# main_1_0.net
KiCad netlist of a schematic drawn in EAGLE
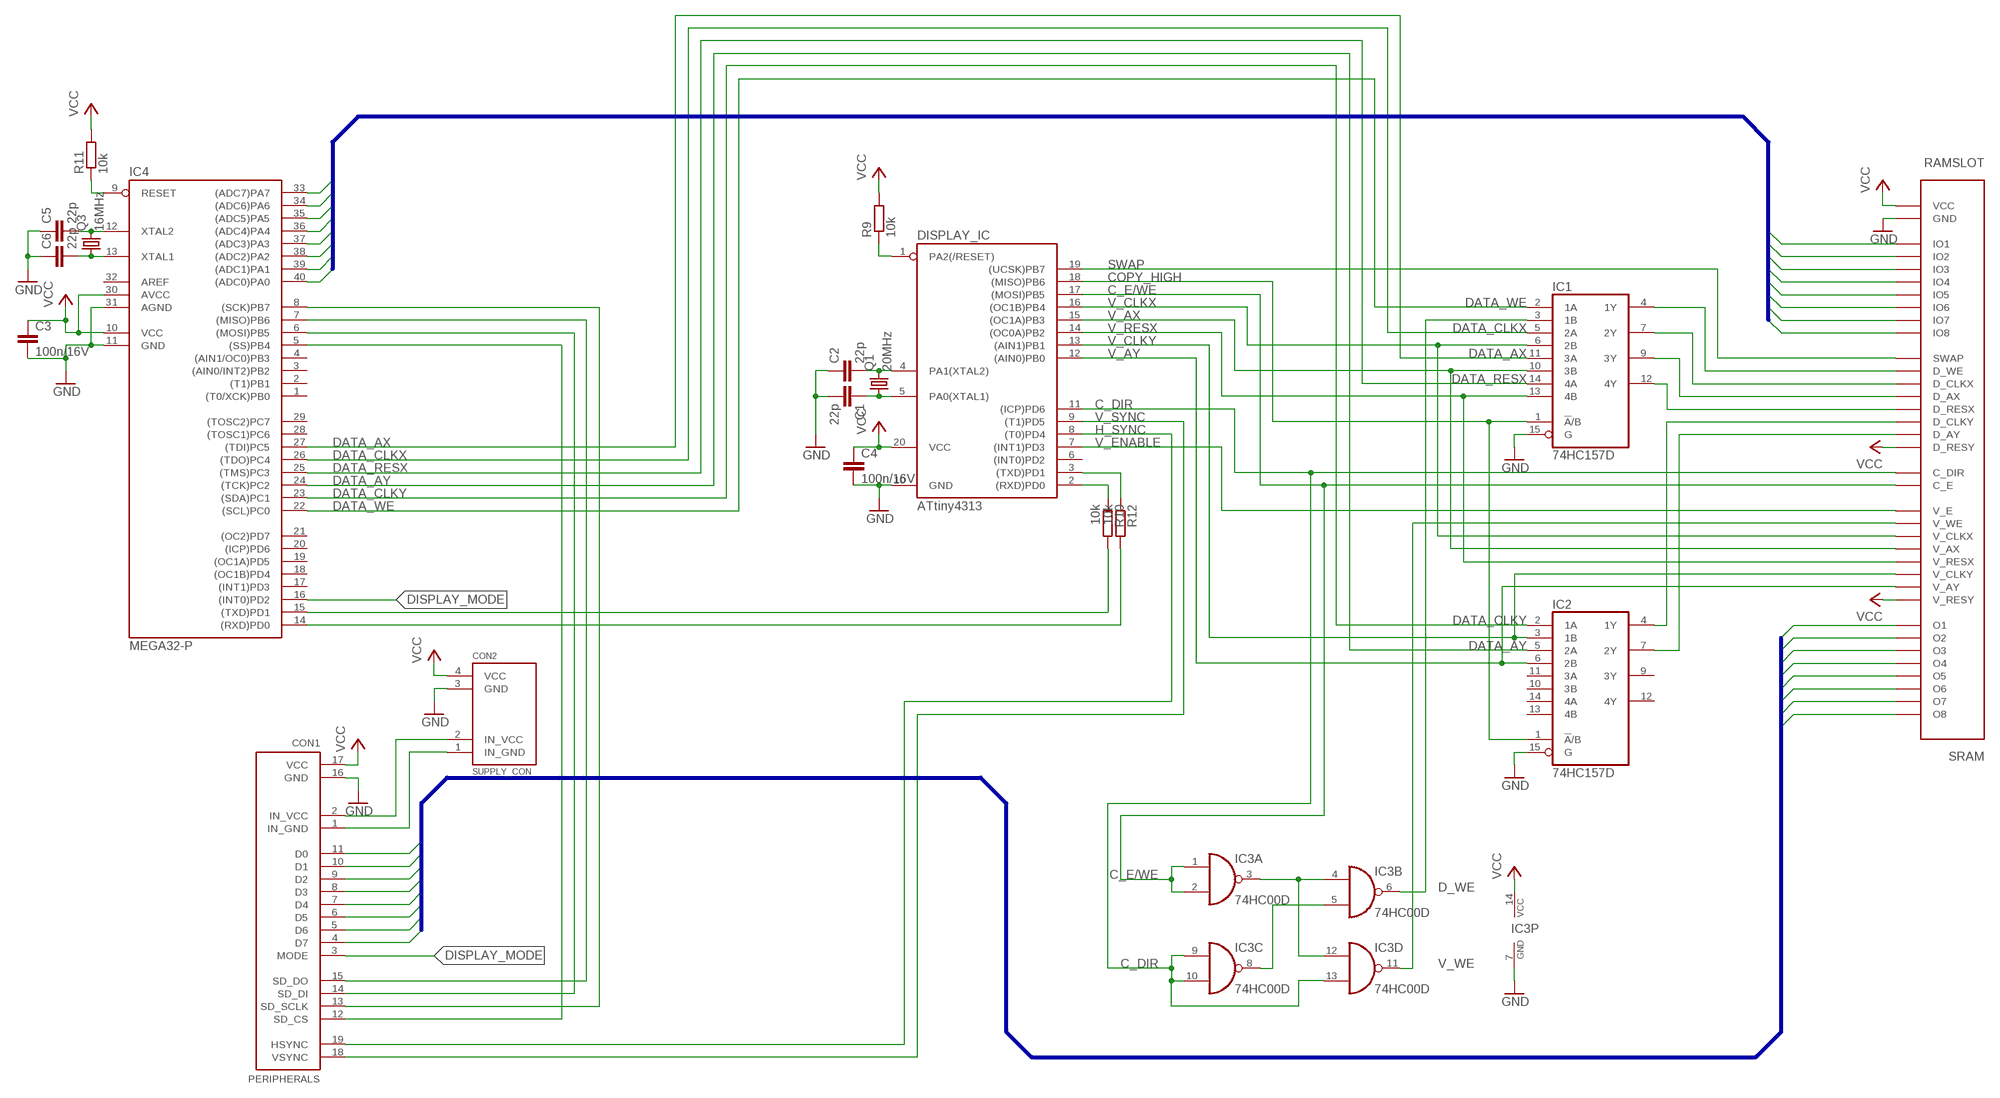
[diagram p0: schematic, sheet 1]

(export (version "E")
  (design (tool "Eeschema 10.0.6"))
  (components
    (comp (ref "C1")
      (value "22p")
      (footprint "eagle-import:C0603")
      (libsource (lib "eagle-import") (part "C-EUC0603"))
    )
    (comp (ref "C2")
      (value "22p")
      (footprint "eagle-import:C0603")
      (libsource (lib "eagle-import") (part "C-EUC0603"))
    )
    (comp (ref "C3")
      (value "100n/16V")
      (footprint "eagle-import:C0603")
      (libsource (lib "eagle-import") (part "C-EUC0603"))
    )
    (comp (ref "C4")
      (value "100n/16V")
      (footprint "eagle-import:C0603")
      (libsource (lib "eagle-import") (part "C-EUC0603"))
    )
    (comp (ref "C5")
      (value "22p")
      (footprint "eagle-import:C0603")
      (libsource (lib "eagle-import") (part "C-EUC0603"))
    )
    (comp (ref "C6")
      (value "22p")
      (footprint "eagle-import:C0603")
      (libsource (lib "eagle-import") (part "C-EUC0603"))
    )
    (comp (ref "CON1")
      (value "PERIPHERALS")
      (footprint "eagle-import:PERIPHERALS_CON")
      (libsource (lib "eagle-import") (part "PERIPHERALS"))
    )
    (comp (ref "CON2")
      (value "SUPPLY_CON")
      (footprint "eagle-import:SUPPLY_CON")
      (libsource (lib "eagle-import") (part "SUPPLY_CON"))
    )
    (comp (ref "DISPLAY_IC")
      (value "ATtiny4313")
      (footprint "eagle-import:DIL20")
      (libsource (lib "eagle-import") (part "TINY2313-P"))
    )
    (comp (ref "IC1")
      (value "74HC157D")
      (footprint "eagle-import:SO16")
      (libsource (lib "eagle-import") (part "74157DHC"))
    )
    (comp (ref "IC2")
      (value "74HC157D")
      (footprint "eagle-import:SO16")
      (libsource (lib "eagle-import") (part "74157DHC"))
    )
    (comp (ref "IC3")
      (value "74HC00D")
      (footprint "eagle-import:SO14")
      (libsource (lib "eagle-import") (part "7400DHC"))
    )
    (comp (ref "IC4")
      (value "MEGA32-P")
      (footprint "eagle-import:DIL40")
      (libsource (lib "eagle-import") (part "MEGA32-P"))
    )
    (comp (ref "Q1")
      (value "20MHz")
      (footprint "eagle-import:HC49")
      (libsource (lib "eagle-import") (part "CRYSTALS-NOGND-HC49"))
    )
    (comp (ref "Q3")
      (value "16MHz")
      (footprint "eagle-import:HC49")
      (libsource (lib "eagle-import") (part "CRYSTALS-NOGND-HC49"))
    )
    (comp (ref "R9")
      (value "10k")
      (footprint "eagle-import:R0603")
      (libsource (lib "eagle-import") (part "R-EU_R0603"))
    )
    (comp (ref "R10")
      (value "10k")
      (footprint "eagle-import:R0603")
      (libsource (lib "eagle-import") (part "R-EU_R0603"))
    )
    (comp (ref "R11")
      (value "10k")
      (footprint "eagle-import:R0603")
      (libsource (lib "eagle-import") (part "R-EU_R0603"))
    )
    (comp (ref "R12")
      (value "10k")
      (footprint "eagle-import:R0603")
      (libsource (lib "eagle-import") (part "R-EU_R0603"))
    )
    (comp (ref "RAMSLOT")
      (value "SRAM")
      (footprint "eagle-import:SLOT")
      (libsource (lib "eagle-import") (part "SLOT"))
    )
  )
  (nets
    (net (code "1") (name "/AREF") (class "Default")
      (node (ref "IC4") (pin "32") (pinfunction "AREF_32") (pintype "power_in"))
    )
    (net (code "2") (name "/COPY_HIGH") (class "Default")
      (node (ref "DISPLAY_IC") (pin "18") (pinfunction "(MISO)PB6_18") (pintype "bidirectional"))
      (node (ref "IC1") (pin "1") (pinfunction "~{A}/B_1") (pintype "input"))
      (node (ref "IC2") (pin "1") (pinfunction "~{A}/B_1") (pintype "input"))
    )
    (net (code "3") (name "/C_DIR") (class "Default")
      (node (ref "DISPLAY_IC") (pin "11") (pinfunction "(ICP)PD6_11") (pintype "bidirectional"))
      (node (ref "IC3") (pin "10") (pinfunction "I1_10") (pintype "input"))
      (node (ref "IC3") (pin "13") (pinfunction "I1_13") (pintype "input"))
      (node (ref "IC3") (pin "9") (pinfunction "I0_9") (pintype "input"))
      (node (ref "RAMSLOT") (pin "C_DIR") (pinfunction "C_DIR_C_DIR") (pintype "bidirectional"))
      (node (ref "RAMSLOT") (pin "C_DIRB") (pinfunction "C_DIR_C_DIRB") (pintype "bidirectional"))
    )
    (net (code "4") (name "/C_E{slash}WE") (class "Default")
      (node (ref "DISPLAY_IC") (pin "17") (pinfunction "(MOSI)PB5_17") (pintype "bidirectional"))
      (node (ref "IC3") (pin "1") (pinfunction "I0_1") (pintype "input"))
      (node (ref "IC3") (pin "2") (pinfunction "I1_2") (pintype "input"))
      (node (ref "RAMSLOT") (pin "C_E") (pinfunction "C_E_C_E") (pintype "bidirectional"))
      (node (ref "RAMSLOT") (pin "C_EB") (pinfunction "C_E_C_EB") (pintype "bidirectional"))
    )
    (net (code "5") (name "/DATA0") (class "Default")
      (node (ref "IC4") (pin "40") (pinfunction "(ADC0)PA0_40") (pintype "bidirectional"))
      (node (ref "RAMSLOT") (pin "IO1") (pinfunction "IO1_IO1") (pintype "bidirectional"))
      (node (ref "RAMSLOT") (pin "IO1B") (pinfunction "IO1_IO1B") (pintype "bidirectional"))
    )
    (net (code "6") (name "/DATA1") (class "Default")
      (node (ref "IC4") (pin "39") (pinfunction "(ADC1)PA1_39") (pintype "bidirectional"))
      (node (ref "RAMSLOT") (pin "IO2") (pinfunction "IO2_IO2") (pintype "bidirectional"))
      (node (ref "RAMSLOT") (pin "IO2B") (pinfunction "IO2_IO2B") (pintype "bidirectional"))
    )
    (net (code "7") (name "/DATA2") (class "Default")
      (node (ref "IC4") (pin "38") (pinfunction "(ADC2)PA2_38") (pintype "bidirectional"))
      (node (ref "RAMSLOT") (pin "IO3") (pinfunction "IO3_IO3") (pintype "bidirectional"))
      (node (ref "RAMSLOT") (pin "IO3B") (pinfunction "IO3_IO3B") (pintype "bidirectional"))
    )
    (net (code "8") (name "/DATA3") (class "Default")
      (node (ref "IC4") (pin "37") (pinfunction "(ADC3)PA3_37") (pintype "bidirectional"))
      (node (ref "RAMSLOT") (pin "IO4") (pinfunction "IO4_IO4") (pintype "bidirectional"))
      (node (ref "RAMSLOT") (pin "IO4B") (pinfunction "IO4_IO4B") (pintype "bidirectional"))
    )
    (net (code "9") (name "/DATA4") (class "Default")
      (node (ref "IC4") (pin "36") (pinfunction "(ADC4)PA4_36") (pintype "bidirectional"))
      (node (ref "RAMSLOT") (pin "IO5") (pinfunction "IO5_IO5") (pintype "bidirectional"))
      (node (ref "RAMSLOT") (pin "IO5B") (pinfunction "IO5_IO5B") (pintype "bidirectional"))
    )
    (net (code "10") (name "/DATA5") (class "Default")
      (node (ref "IC4") (pin "35") (pinfunction "(ADC5)PA5_35") (pintype "bidirectional"))
      (node (ref "RAMSLOT") (pin "IO6") (pinfunction "IO6_IO6") (pintype "bidirectional"))
      (node (ref "RAMSLOT") (pin "IO6B") (pinfunction "IO6_IO6B") (pintype "bidirectional"))
    )
    (net (code "11") (name "/DATA6") (class "Default")
      (node (ref "IC4") (pin "34") (pinfunction "(ADC6)PA6_34") (pintype "bidirectional"))
      (node (ref "RAMSLOT") (pin "IO7") (pinfunction "IO7_IO7") (pintype "bidirectional"))
      (node (ref "RAMSLOT") (pin "IO7B") (pinfunction "IO7_IO7B") (pintype "bidirectional"))
    )
    (net (code "12") (name "/DATA7") (class "Default")
      (node (ref "IC4") (pin "33") (pinfunction "(ADC7)PA7_33") (pintype "bidirectional"))
      (node (ref "RAMSLOT") (pin "IO8") (pinfunction "IO8_IO8") (pintype "bidirectional"))
      (node (ref "RAMSLOT") (pin "IO8B") (pinfunction "IO8_IO8B") (pintype "bidirectional"))
    )
    (net (code "13") (name "/DATA_AX") (class "Default")
      (node (ref "IC1") (pin "11") (pinfunction "3A_11") (pintype "input"))
      (node (ref "IC4") (pin "27") (pinfunction "(TDI)PC5_27") (pintype "bidirectional"))
    )
    (net (code "14") (name "/DATA_AY") (class "Default")
      (node (ref "IC2") (pin "5") (pinfunction "2A_5") (pintype "input"))
      (node (ref "IC4") (pin "24") (pinfunction "(TCK)PC2_24") (pintype "bidirectional"))
    )
    (net (code "15") (name "/DATA_CLKX") (class "Default")
      (node (ref "IC1") (pin "5") (pinfunction "2A_5") (pintype "input"))
      (node (ref "IC4") (pin "26") (pinfunction "(TDO)PC4_26") (pintype "bidirectional"))
    )
    (net (code "16") (name "/DATA_CLKY") (class "Default")
      (node (ref "IC2") (pin "2") (pinfunction "1A_2") (pintype "input"))
      (node (ref "IC4") (pin "23") (pinfunction "(SDA)PC1_23") (pintype "bidirectional"))
    )
    (net (code "17") (name "/DATA_RESX") (class "Default")
      (node (ref "IC1") (pin "14") (pinfunction "4A_14") (pintype "input"))
      (node (ref "IC4") (pin "25") (pinfunction "(TMS)PC3_25") (pintype "bidirectional"))
    )
    (net (code "18") (name "/DATA_WE") (class "Default")
      (node (ref "IC1") (pin "2") (pinfunction "1A_2") (pintype "input"))
      (node (ref "IC4") (pin "22") (pinfunction "(SCL)PC0_22") (pintype "bidirectional"))
    )
    (net (code "19") (name "/D_WE") (class "Default")
      (node (ref "IC1") (pin "3") (pinfunction "1B_3") (pintype "input"))
      (node (ref "IC3") (pin "6") (pinfunction "O_6") (pintype "output"))
    )
    (net (code "20") (name "/H_SYNC") (class "Default")
      (node (ref "CON1") (pin "19") (pinfunction "HSYNC_19") (pintype "bidirectional"))
      (node (ref "DISPLAY_IC") (pin "8") (pinfunction "(T0)PD4_8") (pintype "bidirectional"))
    )
    (net (code "21") (name "/O0") (class "Default")
      (node (ref "CON1") (pin "11") (pinfunction "D0_11") (pintype "bidirectional"))
      (node (ref "RAMSLOT") (pin "O1") (pinfunction "O1_O1") (pintype "bidirectional"))
      (node (ref "RAMSLOT") (pin "O1B") (pinfunction "O1_O1B") (pintype "bidirectional"))
    )
    (net (code "22") (name "/O1") (class "Default")
      (node (ref "CON1") (pin "10") (pinfunction "D1_10") (pintype "bidirectional"))
      (node (ref "RAMSLOT") (pin "O2") (pinfunction "O2_O2") (pintype "bidirectional"))
      (node (ref "RAMSLOT") (pin "O2B") (pinfunction "O2_O2B") (pintype "bidirectional"))
    )
    (net (code "23") (name "/O2") (class "Default")
      (node (ref "CON1") (pin "9") (pinfunction "D2_9") (pintype "bidirectional"))
      (node (ref "RAMSLOT") (pin "O3") (pinfunction "O3_O3") (pintype "bidirectional"))
      (node (ref "RAMSLOT") (pin "O3B") (pinfunction "O3_O3B") (pintype "bidirectional"))
    )
    (net (code "24") (name "/O3") (class "Default")
      (node (ref "CON1") (pin "8") (pinfunction "D3_8") (pintype "bidirectional"))
      (node (ref "RAMSLOT") (pin "O4") (pinfunction "O4_O4") (pintype "bidirectional"))
      (node (ref "RAMSLOT") (pin "O4B") (pinfunction "O4_O4B") (pintype "bidirectional"))
    )
    (net (code "25") (name "/O4") (class "Default")
      (node (ref "CON1") (pin "7") (pinfunction "D4_7") (pintype "bidirectional"))
      (node (ref "RAMSLOT") (pin "O5") (pinfunction "O5_O5") (pintype "bidirectional"))
      (node (ref "RAMSLOT") (pin "O5B") (pinfunction "O5_O5B") (pintype "bidirectional"))
    )
    (net (code "26") (name "/O5") (class "Default")
      (node (ref "CON1") (pin "6") (pinfunction "D5_6") (pintype "bidirectional"))
      (node (ref "RAMSLOT") (pin "O6") (pinfunction "O6_O6") (pintype "bidirectional"))
      (node (ref "RAMSLOT") (pin "O6B") (pinfunction "O6_O6B") (pintype "bidirectional"))
    )
    (net (code "27") (name "/O6") (class "Default")
      (node (ref "CON1") (pin "5") (pinfunction "D6_5") (pintype "bidirectional"))
      (node (ref "RAMSLOT") (pin "O7") (pinfunction "O7_O7") (pintype "bidirectional"))
      (node (ref "RAMSLOT") (pin "O7B") (pinfunction "O7_O7B") (pintype "bidirectional"))
    )
    (net (code "28") (name "/O7") (class "Default")
      (node (ref "CON1") (pin "4") (pinfunction "D7_4") (pintype "bidirectional"))
      (node (ref "RAMSLOT") (pin "O8") (pinfunction "O8_O8") (pintype "bidirectional"))
      (node (ref "RAMSLOT") (pin "O8B") (pinfunction "O8_O8B") (pintype "bidirectional"))
    )
    (net (code "29") (name "/SWAP") (class "Default")
      (node (ref "DISPLAY_IC") (pin "19") (pinfunction "(UCSK)PB7_19") (pintype "bidirectional"))
      (node (ref "RAMSLOT") (pin "SWAP") (pinfunction "SWAP_SWAP") (pintype "bidirectional"))
      (node (ref "RAMSLOT") (pin "SWAPB") (pinfunction "SWAP_SWAPB") (pintype "bidirectional"))
    )
    (net (code "30") (name "/V_AX") (class "Default")
      (node (ref "DISPLAY_IC") (pin "15") (pinfunction "(OC1A)PB3_15") (pintype "bidirectional"))
      (node (ref "IC1") (pin "10") (pinfunction "3B_10") (pintype "input"))
      (node (ref "RAMSLOT") (pin "V_AX") (pinfunction "V_AX_V_AX") (pintype "bidirectional"))
      (node (ref "RAMSLOT") (pin "V_AXB") (pinfunction "V_AX_V_AXB") (pintype "bidirectional"))
    )
    (net (code "31") (name "/V_AY") (class "Default")
      (node (ref "DISPLAY_IC") (pin "12") (pinfunction "(AIN0)PB0_12") (pintype "bidirectional"))
      (node (ref "IC2") (pin "6") (pinfunction "2B_6") (pintype "input"))
      (node (ref "RAMSLOT") (pin "V_AY") (pinfunction "V_AY_V_AY") (pintype "bidirectional"))
      (node (ref "RAMSLOT") (pin "V_AYB") (pinfunction "V_AY_V_AYB") (pintype "bidirectional"))
    )
    (net (code "32") (name "/V_CLKX") (class "Default")
      (node (ref "DISPLAY_IC") (pin "16") (pinfunction "(OC1B)PB4_16") (pintype "bidirectional"))
      (node (ref "IC1") (pin "6") (pinfunction "2B_6") (pintype "input"))
      (node (ref "RAMSLOT") (pin "V_CLKX") (pinfunction "V_CLKX_V_CLKX") (pintype "bidirectional"))
      (node (ref "RAMSLOT") (pin "V_CLKXB") (pinfunction "V_CLKX_V_CLKXB") (pintype "bidirectional"))
    )
    (net (code "33") (name "/V_CLKY") (class "Default")
      (node (ref "DISPLAY_IC") (pin "13") (pinfunction "(AIN1)PB1_13") (pintype "bidirectional"))
      (node (ref "IC2") (pin "3") (pinfunction "1B_3") (pintype "input"))
      (node (ref "RAMSLOT") (pin "V_CLKY") (pinfunction "V_CLKY_V_CLKY") (pintype "bidirectional"))
      (node (ref "RAMSLOT") (pin "V_CLKYB") (pinfunction "V_CLKY_V_CLKYB") (pintype "bidirectional"))
    )
    (net (code "34") (name "/V_ENABLE") (class "Default")
      (node (ref "DISPLAY_IC") (pin "7") (pinfunction "(INT1)PD3_7") (pintype "bidirectional"))
      (node (ref "RAMSLOT") (pin "V_E") (pinfunction "V_E_V_E") (pintype "bidirectional"))
      (node (ref "RAMSLOT") (pin "V_EB") (pinfunction "V_E_V_EB") (pintype "bidirectional"))
    )
    (net (code "35") (name "/V_RESX") (class "Default")
      (node (ref "DISPLAY_IC") (pin "14") (pinfunction "(OC0A)PB2_14") (pintype "bidirectional"))
      (node (ref "IC1") (pin "13") (pinfunction "4B_13") (pintype "input"))
      (node (ref "RAMSLOT") (pin "V_RESX") (pinfunction "V_RESX_V_RESX") (pintype "bidirectional"))
      (node (ref "RAMSLOT") (pin "V_RESXB") (pinfunction "V_RESX_V_RESXB") (pintype "bidirectional"))
    )
    (net (code "36") (name "/V_SYNC") (class "Default")
      (node (ref "CON1") (pin "18") (pinfunction "VSYNC_18") (pintype "bidirectional"))
      (node (ref "DISPLAY_IC") (pin "9") (pinfunction "(T1)PD5_9") (pintype "bidirectional"))
    )
    (net (code "37") (name "/V_WE") (class "Default")
      (node (ref "IC3") (pin "11") (pinfunction "O_11") (pintype "output"))
      (node (ref "RAMSLOT") (pin "V_WE") (pinfunction "V_WE_V_WE") (pintype "bidirectional"))
      (node (ref "RAMSLOT") (pin "V_WEB") (pinfunction "V_WE_V_WEB") (pintype "bidirectional"))
    )
    (net (code "38") (name "DISPLAY_MODE") (class "Default")
      (node (ref "CON1") (pin "3") (pinfunction "MODE_3") (pintype "bidirectional"))
      (node (ref "IC4") (pin "16") (pinfunction "(INT0)PD2_16") (pintype "bidirectional"))
    )
    (net (code "39") (name "GND") (class "Default")
      (node (ref "C1") (pin "2") (pinfunction "2_2") (pintype "passive"))
      (node (ref "C2") (pin "1") (pinfunction "1_1") (pintype "passive"))
      (node (ref "C3") (pin "2") (pinfunction "2_2") (pintype "passive"))
      (node (ref "C4") (pin "2") (pinfunction "2_2") (pintype "passive"))
      (node (ref "C5") (pin "1") (pinfunction "1_1") (pintype "passive"))
      (node (ref "C6") (pin "1") (pinfunction "1_1") (pintype "passive"))
      (node (ref "CON1") (pin "16") (pinfunction "GND_16") (pintype "power_in"))
      (node (ref "CON2") (pin "3") (pinfunction "GND_3") (pintype "bidirectional"))
      (node (ref "DISPLAY_IC") (pin "10") (pinfunction "GND_10") (pintype "power_in"))
      (node (ref "IC1") (pin "15") (pinfunction "G_15") (pintype "input"))
      (node (ref "IC2") (pin "15") (pinfunction "G_15") (pintype "input"))
      (node (ref "IC3") (pin "7") (pinfunction "GND_7") (pintype "power_in"))
      (node (ref "IC4") (pin "11") (pinfunction "GND_11") (pintype "power_in"))
      (node (ref "IC4") (pin "31") (pinfunction "AGND_31") (pintype "power_in"))
      (node (ref "RAMSLOT") (pin "GND") (pinfunction "GND_GND") (pintype "bidirectional"))
      (node (ref "RAMSLOT") (pin "GNDB") (pinfunction "GND_GNDB") (pintype "bidirectional"))
    )
    (net (code "40") (name "Net-(CON1-IN_GND)") (class "Default")
      (node (ref "CON1") (pin "1") (pinfunction "IN_GND_1") (pintype "power_in"))
      (node (ref "CON2") (pin "1") (pinfunction "IN_GND_1") (pintype "bidirectional"))
    )
    (net (code "41") (name "Net-(CON1-IN_VCC)") (class "Default")
      (node (ref "CON1") (pin "2") (pinfunction "IN_VCC_2") (pintype "power_in"))
      (node (ref "CON2") (pin "2") (pinfunction "IN_VCC_2") (pintype "bidirectional"))
    )
    (net (code "42") (name "Net-(CON1-SD_CS)") (class "Default")
      (node (ref "CON1") (pin "12") (pinfunction "SD_CS_12") (pintype "bidirectional"))
      (node (ref "IC4") (pin "5") (pinfunction "(SS)PB4_5") (pintype "bidirectional"))
    )
    (net (code "43") (name "Net-(CON1-SD_DI)") (class "Default")
      (node (ref "CON1") (pin "14") (pinfunction "SD_DI_14") (pintype "bidirectional"))
      (node (ref "IC4") (pin "6") (pinfunction "(MOSI)PB5_6") (pintype "bidirectional"))
    )
    (net (code "44") (name "Net-(CON1-SD_DO)") (class "Default")
      (node (ref "CON1") (pin "15") (pinfunction "SD_DO_15") (pintype "bidirectional"))
      (node (ref "IC4") (pin "7") (pinfunction "(MISO)PB6_7") (pintype "bidirectional"))
    )
    (net (code "45") (name "Net-(CON1-SD_SCLK)") (class "Default")
      (node (ref "CON1") (pin "13") (pinfunction "SD_SCLK_13") (pintype "bidirectional"))
      (node (ref "IC4") (pin "8") (pinfunction "(SCK)PB7_8") (pintype "bidirectional"))
    )
    (net (code "46") (name "Net-(DISPLAY_IC-(RXD)PD0)") (class "Default")
      (node (ref "DISPLAY_IC") (pin "2") (pinfunction "(RXD)PD0_2") (pintype "bidirectional"))
      (node (ref "R10") (pin "1") (pinfunction "1_1") (pintype "passive"))
    )
    (net (code "47") (name "Net-(DISPLAY_IC-(TXD)PD1)") (class "Default")
      (node (ref "DISPLAY_IC") (pin "3") (pinfunction "(TXD)PD1_3") (pintype "bidirectional"))
      (node (ref "R12") (pin "1") (pinfunction "1_1") (pintype "passive"))
    )
    (net (code "48") (name "Net-(DISPLAY_IC-PA0(XTAL1))") (class "Default")
      (node (ref "C1") (pin "1") (pinfunction "1_1") (pintype "passive"))
      (node (ref "DISPLAY_IC") (pin "5") (pinfunction "PA0(XTAL1)_5") (pintype "bidirectional"))
      (node (ref "Q1") (pin "1") (pinfunction "1_1") (pintype "passive"))
    )
    (net (code "49") (name "Net-(DISPLAY_IC-PA1(XTAL2))") (class "Default")
      (node (ref "C2") (pin "2") (pinfunction "2_2") (pintype "passive"))
      (node (ref "DISPLAY_IC") (pin "4") (pinfunction "PA1(XTAL2)_4") (pintype "bidirectional"))
      (node (ref "Q1") (pin "2") (pinfunction "2_2") (pintype "passive"))
    )
    (net (code "50") (name "Net-(DISPLAY_IC-PA2({slash}RESET))") (class "Default")
      (node (ref "DISPLAY_IC") (pin "1") (pinfunction "PA2(/RESET)_1") (pintype "input"))
      (node (ref "R9") (pin "1") (pinfunction "1_1") (pintype "passive"))
    )
    (net (code "51") (name "Net-(IC1A-1Y)") (class "Default")
      (node (ref "IC1") (pin "4") (pinfunction "1Y_4") (pintype "output"))
      (node (ref "RAMSLOT") (pin "D_WE") (pinfunction "D_WE_D_WE") (pintype "bidirectional"))
      (node (ref "RAMSLOT") (pin "D_WEB") (pinfunction "D_WE_D_WEB") (pintype "bidirectional"))
    )
    (net (code "52") (name "Net-(IC1A-2Y)") (class "Default")
      (node (ref "IC1") (pin "7") (pinfunction "2Y_7") (pintype "output"))
      (node (ref "RAMSLOT") (pin "D_CLKX") (pinfunction "D_CLKX_D_CLKX") (pintype "bidirectional"))
      (node (ref "RAMSLOT") (pin "D_CLKXB") (pinfunction "D_CLKX_D_CLKXB") (pintype "bidirectional"))
    )
    (net (code "53") (name "Net-(IC1A-3Y)") (class "Default")
      (node (ref "IC1") (pin "9") (pinfunction "3Y_9") (pintype "output"))
      (node (ref "RAMSLOT") (pin "D_AX") (pinfunction "D_AX_D_AX") (pintype "bidirectional"))
      (node (ref "RAMSLOT") (pin "D_AXB") (pinfunction "D_AX_D_AXB") (pintype "bidirectional"))
    )
    (net (code "54") (name "Net-(IC1A-4Y)") (class "Default")
      (node (ref "IC1") (pin "12") (pinfunction "4Y_12") (pintype "output"))
      (node (ref "RAMSLOT") (pin "D_RESX") (pinfunction "D_RESX_D_RESX") (pintype "bidirectional"))
      (node (ref "RAMSLOT") (pin "D_RESXB") (pinfunction "D_RESX_D_RESXB") (pintype "bidirectional"))
    )
    (net (code "55") (name "Net-(IC2A-1Y)") (class "Default")
      (node (ref "IC2") (pin "4") (pinfunction "1Y_4") (pintype "output"))
      (node (ref "RAMSLOT") (pin "D_CLKY") (pinfunction "D_CLKY_D_CLKY") (pintype "bidirectional"))
      (node (ref "RAMSLOT") (pin "D_CLKYB") (pinfunction "D_CLKY_D_CLKYB") (pintype "bidirectional"))
    )
    (net (code "56") (name "Net-(IC2A-2Y)") (class "Default")
      (node (ref "IC2") (pin "7") (pinfunction "2Y_7") (pintype "output"))
      (node (ref "RAMSLOT") (pin "D_AY") (pinfunction "D_AY_D_AY") (pintype "bidirectional"))
      (node (ref "RAMSLOT") (pin "D_AYB") (pinfunction "D_AY_D_AYB") (pintype "bidirectional"))
    )
    (net (code "57") (name "Net-(IC3A-O)") (class "Default")
      (node (ref "IC3") (pin "12") (pinfunction "I0_12") (pintype "input"))
      (node (ref "IC3") (pin "3") (pinfunction "O_3") (pintype "output"))
      (node (ref "IC3") (pin "4") (pinfunction "I0_4") (pintype "input"))
    )
    (net (code "58") (name "Net-(IC3B-I1)") (class "Default")
      (node (ref "IC3") (pin "5") (pinfunction "I1_5") (pintype "input"))
      (node (ref "IC3") (pin "8") (pinfunction "O_8") (pintype "output"))
    )
    (net (code "59") (name "Net-(IC4-(RXD)PD0)") (class "Default")
      (node (ref "IC4") (pin "14") (pinfunction "(RXD)PD0_14") (pintype "bidirectional"))
      (node (ref "R12") (pin "2") (pinfunction "2_2") (pintype "passive"))
    )
    (net (code "60") (name "Net-(IC4-(TXD)PD1)") (class "Default")
      (node (ref "IC4") (pin "15") (pinfunction "(TXD)PD1_15") (pintype "bidirectional"))
      (node (ref "R10") (pin "2") (pinfunction "2_2") (pintype "passive"))
    )
    (net (code "61") (name "Net-(IC4-RESET)") (class "Default")
      (node (ref "IC4") (pin "9") (pinfunction "RESET_9") (pintype "input"))
      (node (ref "R11") (pin "1") (pinfunction "1_1") (pintype "passive"))
    )
    (net (code "62") (name "Net-(IC4-XTAL1)") (class "Default")
      (node (ref "C6") (pin "2") (pinfunction "2_2") (pintype "passive"))
      (node (ref "IC4") (pin "13") (pinfunction "XTAL1_13") (pintype "bidirectional"))
      (node (ref "Q3") (pin "1") (pinfunction "1_1") (pintype "passive"))
    )
    (net (code "63") (name "Net-(IC4-XTAL2)") (class "Default")
      (node (ref "C5") (pin "2") (pinfunction "2_2") (pintype "passive"))
      (node (ref "IC4") (pin "12") (pinfunction "XTAL2_12") (pintype "bidirectional"))
      (node (ref "Q3") (pin "2") (pinfunction "2_2") (pintype "passive"))
    )
    (net (code "64") (name "VCC") (class "Default")
      (node (ref "C3") (pin "1") (pinfunction "1_1") (pintype "passive"))
      (node (ref "C4") (pin "1") (pinfunction "1_1") (pintype "passive"))
      (node (ref "CON1") (pin "17") (pinfunction "VCC_17") (pintype "power_in"))
      (node (ref "CON2") (pin "4") (pinfunction "VCC_4") (pintype "bidirectional"))
      (node (ref "DISPLAY_IC") (pin "20") (pinfunction "VCC_20") (pintype "power_in"))
      (node (ref "IC3") (pin "14") (pinfunction "VCC_14") (pintype "power_in"))
      (node (ref "IC4") (pin "10") (pinfunction "VCC_10") (pintype "power_in"))
      (node (ref "IC4") (pin "30") (pinfunction "AVCC_30") (pintype "power_in"))
      (node (ref "R11") (pin "2") (pinfunction "2_2") (pintype "passive"))
      (node (ref "R9") (pin "2") (pinfunction "2_2") (pintype "passive"))
      (node (ref "RAMSLOT") (pin "D_RESY") (pinfunction "D_RESY_D_RESY") (pintype "bidirectional"))
      (node (ref "RAMSLOT") (pin "D_RESYB") (pinfunction "D_RESY_D_RESYB") (pintype "bidirectional"))
      (node (ref "RAMSLOT") (pin "VCC") (pinfunction "VCC_VCC") (pintype "bidirectional"))
      (node (ref "RAMSLOT") (pin "VCCB") (pinfunction "VCC_VCCB") (pintype "bidirectional"))
      (node (ref "RAMSLOT") (pin "V_RESY") (pinfunction "V_RESY_V_RESY") (pintype "bidirectional"))
      (node (ref "RAMSLOT") (pin "V_RESYB") (pinfunction "V_RESY_V_RESYB") (pintype "bidirectional"))
    )
    (net (code "65") (name "unconnected-(DISPLAY_IC-(INT0)PD2-Pad6)") (class "Default")
      (node (ref "DISPLAY_IC") (pin "6") (pinfunction "(INT0)PD2_6") (pintype "bidirectional"))
    )
    (net (code "66") (name "unconnected-(IC2A-3A-Pad11)") (class "Default")
      (node (ref "IC2") (pin "11") (pinfunction "3A_11") (pintype "input"))
    )
    (net (code "67") (name "unconnected-(IC2A-3B-Pad10)") (class "Default")
      (node (ref "IC2") (pin "10") (pinfunction "3B_10") (pintype "input"))
    )
    (net (code "68") (name "unconnected-(IC2A-3Y-Pad9)") (class "Default")
      (node (ref "IC2") (pin "9") (pinfunction "3Y_9") (pintype "output"))
    )
    (net (code "69") (name "unconnected-(IC2A-4A-Pad14)") (class "Default")
      (node (ref "IC2") (pin "14") (pinfunction "4A_14") (pintype "input"))
    )
    (net (code "70") (name "unconnected-(IC2A-4B-Pad13)") (class "Default")
      (node (ref "IC2") (pin "13") (pinfunction "4B_13") (pintype "input"))
    )
    (net (code "71") (name "unconnected-(IC2A-4Y-Pad12)") (class "Default")
      (node (ref "IC2") (pin "12") (pinfunction "4Y_12") (pintype "output"))
    )
    (net (code "72") (name "unconnected-(IC4-(AIN0{slash}INT2)PB2-Pad3)") (class "Default")
      (node (ref "IC4") (pin "3") (pinfunction "(AIN0/INT2)PB2_3") (pintype "bidirectional"))
    )
    (net (code "73") (name "unconnected-(IC4-(AIN1{slash}OC0)PB3-Pad4)") (class "Default")
      (node (ref "IC4") (pin "4") (pinfunction "(AIN1/OC0)PB3_4") (pintype "bidirectional"))
    )
    (net (code "74") (name "unconnected-(IC4-(ICP)PD6-Pad20)") (class "Default")
      (node (ref "IC4") (pin "20") (pinfunction "(ICP)PD6_20") (pintype "bidirectional"))
    )
    (net (code "75") (name "unconnected-(IC4-(INT1)PD3-Pad17)") (class "Default")
      (node (ref "IC4") (pin "17") (pinfunction "(INT1)PD3_17") (pintype "bidirectional"))
    )
    (net (code "76") (name "unconnected-(IC4-(OC1A)PD5-Pad19)") (class "Default")
      (node (ref "IC4") (pin "19") (pinfunction "(OC1A)PD5_19") (pintype "bidirectional"))
    )
    (net (code "77") (name "unconnected-(IC4-(OC1B)PD4-Pad18)") (class "Default")
      (node (ref "IC4") (pin "18") (pinfunction "(OC1B)PD4_18") (pintype "bidirectional"))
    )
    (net (code "78") (name "unconnected-(IC4-(OC2)PD7-Pad21)") (class "Default")
      (node (ref "IC4") (pin "21") (pinfunction "(OC2)PD7_21") (pintype "bidirectional"))
    )
    (net (code "79") (name "unconnected-(IC4-(T0{slash}XCK)PB0-Pad1)") (class "Default")
      (node (ref "IC4") (pin "1") (pinfunction "(T0/XCK)PB0_1") (pintype "bidirectional"))
    )
    (net (code "80") (name "unconnected-(IC4-(T1)PB1-Pad2)") (class "Default")
      (node (ref "IC4") (pin "2") (pinfunction "(T1)PB1_2") (pintype "bidirectional"))
    )
    (net (code "81") (name "unconnected-(IC4-(TOSC1)PC6-Pad28)") (class "Default")
      (node (ref "IC4") (pin "28") (pinfunction "(TOSC1)PC6_28") (pintype "bidirectional"))
    )
    (net (code "82") (name "unconnected-(IC4-(TOSC2)PC7-Pad29)") (class "Default")
      (node (ref "IC4") (pin "29") (pinfunction "(TOSC2)PC7_29") (pintype "bidirectional"))
    )
  )
)
